# LevelShift.net
KiCad netlist of a schematic drawn in Altium Designer
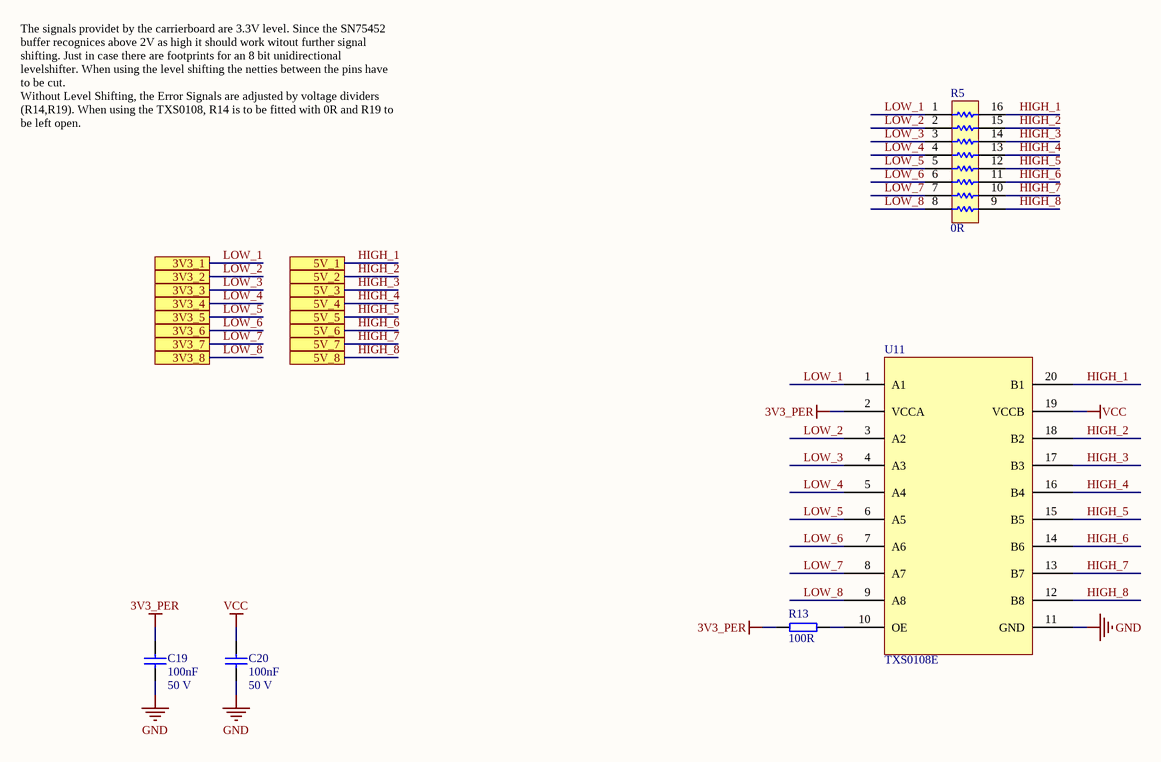
[diagram p0: LevelShift.SchDoc]

(export (version "E")
  (design (tool "Eeschema 10.0.6"))
  (components
    (comp (ref "C19")
      (value "100nF")
      (footprint "C_0603(1608)100_L")
      (description "CAP 0603 (1608 Metric) SMD")
      (fields
        (field (name "TOLERANCE") "±20%")
        (field (name "MF") "Yageo")
        (field (name "RATED VOLTAGE") "50 V")
        (field (name "CREATED") "2018_09_06_AGeiger")
      )
      (libsource (lib "UZOhm_Optical") (part "C_0603"))
    )
    (comp (ref "C20")
      (value "100nF")
      (footprint "C_0603(1608)100_L")
      (description "CAP 0603 (1608 Metric) SMD")
      (fields
        (field (name "TOLERANCE") "±20%")
        (field (name "MF") "Yageo")
        (field (name "RATED VOLTAGE") "50 V")
        (field (name "CREATED") "2018_09_06_AGeiger")
      )
      (libsource (lib "UZOhm_Optical") (part "C_0603"))
    )
    (comp (ref "R5")
      (value "0R")
      (footprint "CAF-50P380X160-16N")
      (description "Chip Resistor Array")
      (fields
        (field (name "MF") "Bourns")
        (field (name "MPN") "CAY16-000J8LF")
        (field (name "CREATED") "2018_10_30_AGeiger")
      )
      (libsource (lib "UZOhm_Optical") (part "R_0402_Array_8R"))
    )
    (comp (ref "R13")
      (value "100R")
      (footprint "R_0603_N")
      (description "SMD Resistor 0603")
      (fields
        (field (name "TOLERANCE") "1%")
        (field (name "VOLTAGE") "75V")
        (field (name "CREATED") "2018_09_06_AGeiger")
      )
      (libsource (lib "UZOhm_Optical") (part "R_0603"))
    )
    (comp (ref "U11")
      (value "TXS0108E")
      (footprint "TXS0108E")
      (description "8 Ch. Bidirectional Voltage-Level translator")
      (libsource (lib "UZOhm_Optical") (part "TXS0108E"))
    )
  )
  (nets
    (net (code "1") (name "/HIGH_1") (class "Default")
      (node (ref "R5") (pin "16") (pinfunction "16_16") (pintype "passive"))
      (node (ref "U11") (pin "20") (pinfunction "B1_20") (pintype "passive"))
    )
    (net (code "2") (name "/HIGH_2") (class "Default")
      (node (ref "R5") (pin "15") (pinfunction "15_15") (pintype "passive"))
      (node (ref "U11") (pin "18") (pinfunction "B2_18") (pintype "passive"))
    )
    (net (code "3") (name "/HIGH_3") (class "Default")
      (node (ref "R5") (pin "14") (pinfunction "14_14") (pintype "passive"))
      (node (ref "U11") (pin "17") (pinfunction "B3_17") (pintype "passive"))
    )
    (net (code "4") (name "/HIGH_4") (class "Default")
      (node (ref "R5") (pin "13") (pinfunction "13_13") (pintype "passive"))
      (node (ref "U11") (pin "16") (pinfunction "B4_16") (pintype "passive"))
    )
    (net (code "5") (name "/HIGH_5") (class "Default")
      (node (ref "R5") (pin "12") (pinfunction "12_12") (pintype "passive"))
      (node (ref "U11") (pin "15") (pinfunction "B5_15") (pintype "passive"))
    )
    (net (code "6") (name "/HIGH_6") (class "Default")
      (node (ref "R5") (pin "11") (pinfunction "11_11") (pintype "passive"))
      (node (ref "U11") (pin "14") (pinfunction "B6_14") (pintype "passive"))
    )
    (net (code "7") (name "/HIGH_7") (class "Default")
      (node (ref "R5") (pin "10") (pinfunction "10_10") (pintype "passive"))
      (node (ref "U11") (pin "13") (pinfunction "B7_13") (pintype "passive"))
    )
    (net (code "8") (name "/HIGH_8") (class "Default")
      (node (ref "R5") (pin "9") (pinfunction "9_9") (pintype "passive"))
      (node (ref "U11") (pin "12") (pinfunction "B8_12") (pintype "passive"))
    )
    (net (code "9") (name "/LOW_1") (class "Default")
      (node (ref "R5") (pin "1") (pinfunction "1_1") (pintype "passive"))
      (node (ref "U11") (pin "1") (pinfunction "A1_1") (pintype "passive"))
    )
    (net (code "10") (name "/LOW_2") (class "Default")
      (node (ref "R5") (pin "2") (pinfunction "2_2") (pintype "passive"))
      (node (ref "U11") (pin "3") (pinfunction "A2_3") (pintype "passive"))
    )
    (net (code "11") (name "/LOW_3") (class "Default")
      (node (ref "R5") (pin "3") (pinfunction "3_3") (pintype "passive"))
      (node (ref "U11") (pin "4") (pinfunction "A3_4") (pintype "passive"))
    )
    (net (code "12") (name "/LOW_4") (class "Default")
      (node (ref "R5") (pin "4") (pinfunction "4_4") (pintype "passive"))
      (node (ref "U11") (pin "5") (pinfunction "A4_5") (pintype "passive"))
    )
    (net (code "13") (name "/LOW_5") (class "Default")
      (node (ref "R5") (pin "5") (pinfunction "5_5") (pintype "passive"))
      (node (ref "U11") (pin "6") (pinfunction "A5_6") (pintype "passive"))
    )
    (net (code "14") (name "/LOW_6") (class "Default")
      (node (ref "R5") (pin "6") (pinfunction "6_6") (pintype "passive"))
      (node (ref "U11") (pin "7") (pinfunction "A6_7") (pintype "passive"))
    )
    (net (code "15") (name "/LOW_7") (class "Default")
      (node (ref "R5") (pin "7") (pinfunction "7_7") (pintype "passive"))
      (node (ref "U11") (pin "8") (pinfunction "A7_8") (pintype "passive"))
    )
    (net (code "16") (name "/LOW_8") (class "Default")
      (node (ref "R5") (pin "8") (pinfunction "8_8") (pintype "passive"))
      (node (ref "U11") (pin "9") (pinfunction "A8_9") (pintype "passive"))
    )
    (net (code "17") (name "3V3_PER") (class "Default")
      (node (ref "C19") (pin "1") (pinfunction "1_1") (pintype "passive"))
      (node (ref "R13") (pin "1") (pinfunction "1_1") (pintype "passive"))
      (node (ref "U11") (pin "2") (pinfunction "VCCA_2") (pintype "passive"))
    )
    (net (code "18") (name "GND") (class "Default")
      (node (ref "C19") (pin "2") (pinfunction "2_2") (pintype "passive"))
      (node (ref "C20") (pin "2") (pinfunction "2_2") (pintype "passive"))
      (node (ref "U11") (pin "11") (pinfunction "GND_11") (pintype "passive"))
    )
    (net (code "19") (name "Net-(U11-OE)") (class "Default")
      (node (ref "R13") (pin "2") (pinfunction "2_2") (pintype "passive"))
      (node (ref "U11") (pin "10") (pinfunction "OE_10") (pintype "passive"))
    )
    (net (code "20") (name "VCC") (class "Default")
      (node (ref "C20") (pin "1") (pinfunction "1_1") (pintype "passive"))
      (node (ref "U11") (pin "19") (pinfunction "VCCB_19") (pintype "passive"))
    )
  )
)
